# SAMD21E-breakout.net
KiCad netlist of a schematic drawn in EAGLE
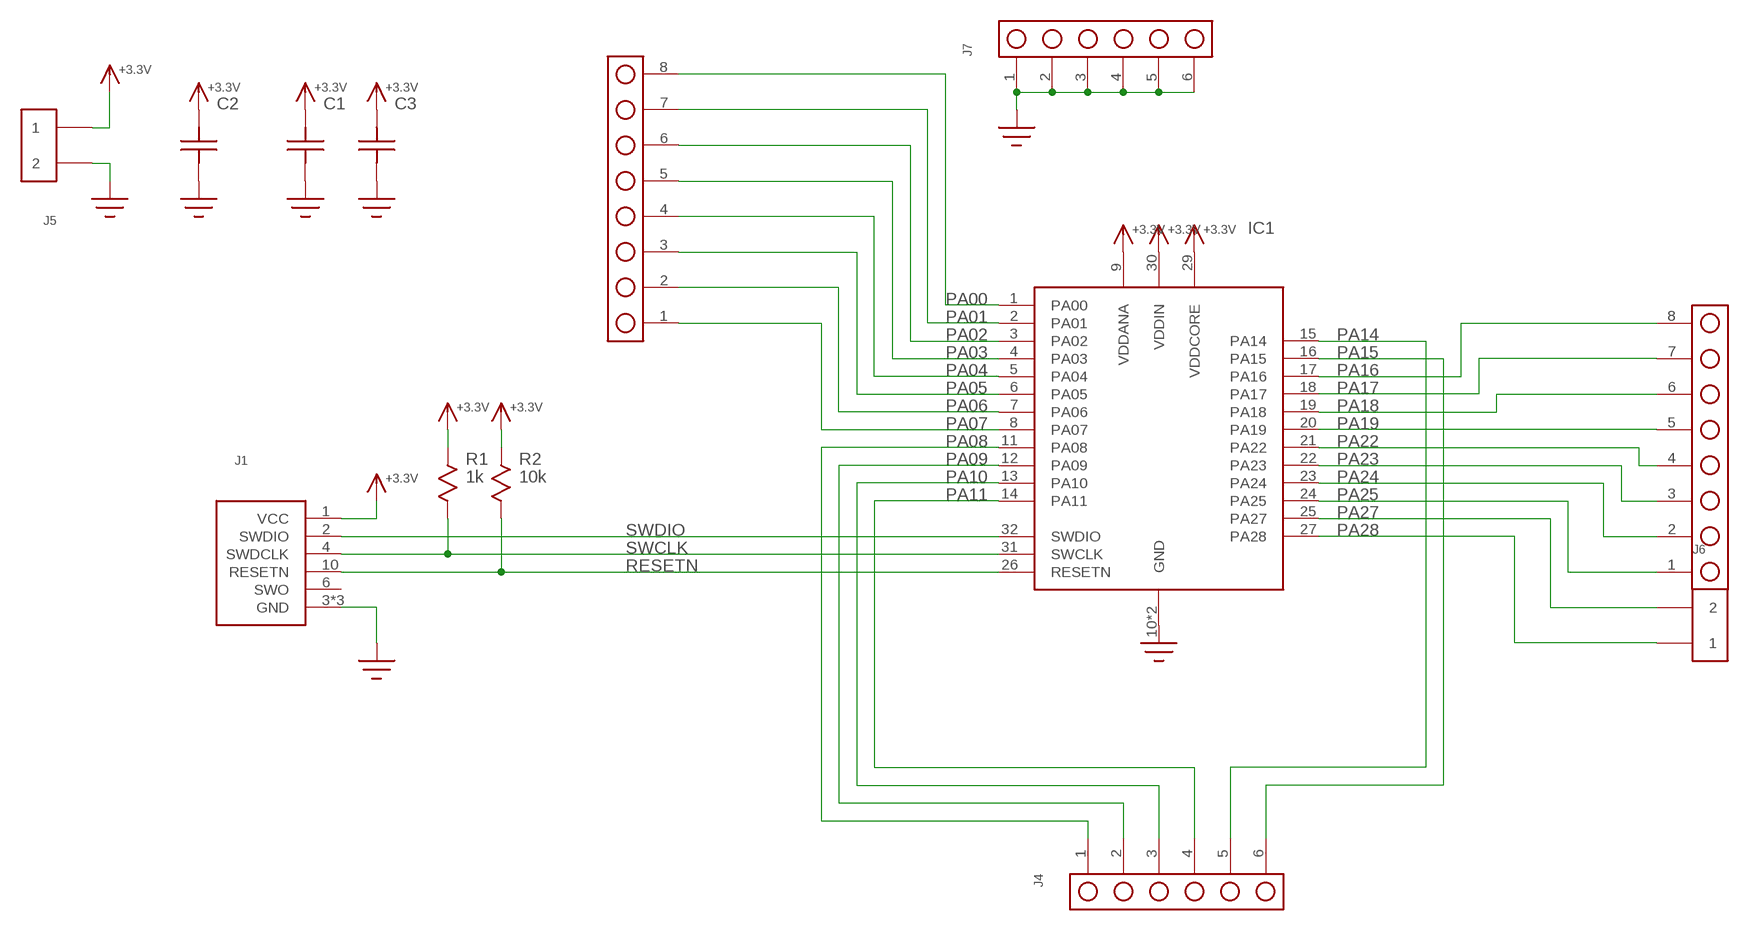
[diagram p0: schematic, sheet 1]

(export (version "E")
  (design (tool "Eeschema 10.0.6"))
  (components
    (comp (ref "C1")
      (value "C0603")
      (footprint "eagle-import:C0603")
      (libsource (lib "eagle-import") (part "C0603"))
    )
    (comp (ref "C2")
      (value "C1206")
      (footprint "eagle-import:1206")
      (libsource (lib "eagle-import") (part "C1206"))
    )
    (comp (ref "C3")
      (value "C0603")
      (footprint "eagle-import:C0603")
      (libsource (lib "eagle-import") (part "C0603"))
    )
    (comp (ref "IC1")
      (value "SAMD21E")
      (footprint "eagle-import:TQFP32_7X7")
      (libsource (lib "eagle-import") (part "SAMD21E"))
    )
    (comp (ref "J1")
      (value "SWD-ICSP-HEADER")
      (footprint "eagle-import:HEADER-2X5-50MIL")
      (libsource (lib "eagle-import") (part "SWD-ICSP-HEADER"))
    )
    (comp (ref "J2")
      (value "HEADER_8PIN")
      (footprint "eagle-import:HEADER_8_PIN")
      (libsource (lib "eagle-import") (part "HEADER_8PIN"))
    )
    (comp (ref "J3")
      (value "HEADER_8PIN")
      (footprint "eagle-import:HEADER_8_PIN")
      (libsource (lib "eagle-import") (part "HEADER_8PIN"))
    )
    (comp (ref "J4")
      (value "HEADER_6PIN")
      (footprint "eagle-import:HEADER_6PIN")
      (libsource (lib "eagle-import") (part "HEADER_6PIN"))
    )
    (comp (ref "J5")
      (value "HEADER_2PIN")
      (footprint "eagle-import:HEADER_2PIN")
      (libsource (lib "eagle-import") (part "HEADER_2PIN"))
    )
    (comp (ref "J6")
      (value "HEADER_2PIN")
      (footprint "eagle-import:HEADER_2PIN")
      (libsource (lib "eagle-import") (part "HEADER_2PIN"))
    )
    (comp (ref "J7")
      (value "HEADER_6PIN")
      (footprint "eagle-import:HEADER_6PIN")
      (libsource (lib "eagle-import") (part "HEADER_6PIN"))
    )
    (comp (ref "R1")
      (value "1k")
      (footprint "eagle-import:R0603")
      (libsource (lib "eagle-import") (part "R0603"))
    )
    (comp (ref "R2")
      (value "10k")
      (footprint "eagle-import:R0603")
      (libsource (lib "eagle-import") (part "R0603"))
    )
  )
  (nets
    (net (code "1") (name "+3.3V") (class "Default")
      (node (ref "C1") (pin "P$2") (pinfunction "P$2_P$2") (pintype "bidirectional"))
      (node (ref "C2") (pin "P$2") (pinfunction "P$2_P$2") (pintype "bidirectional"))
      (node (ref "C3") (pin "P$2") (pinfunction "P$2_P$2") (pintype "bidirectional"))
      (node (ref "IC1") (pin "29") (pinfunction "VDDCORE_29") (pintype "bidirectional"))
      (node (ref "IC1") (pin "30") (pinfunction "VDDIN_30") (pintype "bidirectional"))
      (node (ref "IC1") (pin "9") (pinfunction "VDDANA_9") (pintype "bidirectional"))
      (node (ref "J1") (pin "1") (pinfunction "VCC_1") (pintype "bidirectional"))
      (node (ref "J5") (pin "1") (pinfunction "1_1") (pintype "bidirectional"))
      (node (ref "R1") (pin "P$1") (pinfunction "P$3_P$1") (pintype "bidirectional"))
      (node (ref "R2") (pin "P$1") (pinfunction "P$3_P$1") (pintype "bidirectional"))
    )
    (net (code "2") (name "/PA00") (class "Default")
      (node (ref "IC1") (pin "1") (pinfunction "PA00_1") (pintype "bidirectional"))
      (node (ref "J2") (pin "8") (pinfunction "8_8") (pintype "bidirectional"))
    )
    (net (code "3") (name "/PA01") (class "Default")
      (node (ref "IC1") (pin "2") (pinfunction "PA01_2") (pintype "bidirectional"))
      (node (ref "J2") (pin "7") (pinfunction "7_7") (pintype "bidirectional"))
    )
    (net (code "4") (name "/PA02") (class "Default")
      (node (ref "IC1") (pin "3") (pinfunction "PA02_3") (pintype "bidirectional"))
      (node (ref "J2") (pin "6") (pinfunction "6_6") (pintype "bidirectional"))
    )
    (net (code "5") (name "/PA03") (class "Default")
      (node (ref "IC1") (pin "4") (pinfunction "PA03_4") (pintype "bidirectional"))
      (node (ref "J2") (pin "5") (pinfunction "5_5") (pintype "bidirectional"))
    )
    (net (code "6") (name "/PA04") (class "Default")
      (node (ref "IC1") (pin "5") (pinfunction "PA04_5") (pintype "bidirectional"))
      (node (ref "J2") (pin "4") (pinfunction "4_4") (pintype "bidirectional"))
    )
    (net (code "7") (name "/PA05") (class "Default")
      (node (ref "IC1") (pin "6") (pinfunction "PA05_6") (pintype "bidirectional"))
      (node (ref "J2") (pin "3") (pinfunction "3_3") (pintype "bidirectional"))
    )
    (net (code "8") (name "/PA06") (class "Default")
      (node (ref "IC1") (pin "7") (pinfunction "PA06_7") (pintype "bidirectional"))
      (node (ref "J2") (pin "2") (pinfunction "2_2") (pintype "bidirectional"))
    )
    (net (code "9") (name "/PA07") (class "Default")
      (node (ref "IC1") (pin "8") (pinfunction "PA07_8") (pintype "bidirectional"))
      (node (ref "J2") (pin "1") (pinfunction "1_1") (pintype "bidirectional"))
    )
    (net (code "10") (name "/PA08") (class "Default")
      (node (ref "IC1") (pin "11") (pinfunction "PA08_11") (pintype "bidirectional"))
      (node (ref "J4") (pin "1") (pinfunction "1_1") (pintype "bidirectional"))
    )
    (net (code "11") (name "/PA09") (class "Default")
      (node (ref "IC1") (pin "12") (pinfunction "PA09_12") (pintype "bidirectional"))
      (node (ref "J4") (pin "2") (pinfunction "2_2") (pintype "bidirectional"))
    )
    (net (code "12") (name "/PA10") (class "Default")
      (node (ref "IC1") (pin "13") (pinfunction "PA10_13") (pintype "bidirectional"))
      (node (ref "J4") (pin "3") (pinfunction "3_3") (pintype "bidirectional"))
    )
    (net (code "13") (name "/PA11") (class "Default")
      (node (ref "IC1") (pin "14") (pinfunction "PA11_14") (pintype "bidirectional"))
      (node (ref "J4") (pin "4") (pinfunction "4_4") (pintype "bidirectional"))
    )
    (net (code "14") (name "/PA14") (class "Default")
      (node (ref "IC1") (pin "15") (pinfunction "PA14_15") (pintype "bidirectional"))
      (node (ref "J4") (pin "5") (pinfunction "5_5") (pintype "bidirectional"))
    )
    (net (code "15") (name "/PA15") (class "Default")
      (node (ref "IC1") (pin "16") (pinfunction "PA15_16") (pintype "bidirectional"))
      (node (ref "J4") (pin "6") (pinfunction "6_6") (pintype "bidirectional"))
    )
    (net (code "16") (name "/PA16") (class "Default")
      (node (ref "IC1") (pin "17") (pinfunction "PA16_17") (pintype "bidirectional"))
      (node (ref "J3") (pin "8") (pinfunction "8_8") (pintype "bidirectional"))
    )
    (net (code "17") (name "/PA17") (class "Default")
      (node (ref "IC1") (pin "18") (pinfunction "PA17_18") (pintype "bidirectional"))
      (node (ref "J3") (pin "7") (pinfunction "7_7") (pintype "bidirectional"))
    )
    (net (code "18") (name "/PA18") (class "Default")
      (node (ref "IC1") (pin "19") (pinfunction "PA18_19") (pintype "bidirectional"))
      (node (ref "J3") (pin "6") (pinfunction "6_6") (pintype "bidirectional"))
    )
    (net (code "19") (name "/PA19") (class "Default")
      (node (ref "IC1") (pin "20") (pinfunction "PA19_20") (pintype "bidirectional"))
      (node (ref "J3") (pin "5") (pinfunction "5_5") (pintype "bidirectional"))
    )
    (net (code "20") (name "/PA22") (class "Default")
      (node (ref "IC1") (pin "21") (pinfunction "PA22_21") (pintype "bidirectional"))
      (node (ref "J3") (pin "4") (pinfunction "4_4") (pintype "bidirectional"))
    )
    (net (code "21") (name "/PA23") (class "Default")
      (node (ref "IC1") (pin "22") (pinfunction "PA23_22") (pintype "bidirectional"))
      (node (ref "J3") (pin "3") (pinfunction "3_3") (pintype "bidirectional"))
    )
    (net (code "22") (name "/PA24") (class "Default")
      (node (ref "IC1") (pin "23") (pinfunction "PA24_23") (pintype "bidirectional"))
      (node (ref "J3") (pin "2") (pinfunction "2_2") (pintype "bidirectional"))
    )
    (net (code "23") (name "/PA25") (class "Default")
      (node (ref "IC1") (pin "24") (pinfunction "PA25_24") (pintype "bidirectional"))
      (node (ref "J3") (pin "1") (pinfunction "1_1") (pintype "bidirectional"))
    )
    (net (code "24") (name "/PA27") (class "Default")
      (node (ref "IC1") (pin "25") (pinfunction "PA27_25") (pintype "bidirectional"))
      (node (ref "J6") (pin "2") (pinfunction "2_2") (pintype "bidirectional"))
    )
    (net (code "25") (name "/PA28") (class "Default")
      (node (ref "IC1") (pin "27") (pinfunction "PA28_27") (pintype "bidirectional"))
      (node (ref "J6") (pin "1") (pinfunction "1_1") (pintype "bidirectional"))
    )
    (net (code "26") (name "/RESETN") (class "Default")
      (node (ref "IC1") (pin "26") (pinfunction "RESETN_26") (pintype "bidirectional"))
      (node (ref "J1") (pin "10") (pinfunction "RESETN_10") (pintype "bidirectional"))
      (node (ref "R2") (pin "P$2") (pinfunction "P$4_P$2") (pintype "bidirectional"))
    )
    (net (code "27") (name "/SWCLK") (class "Default")
      (node (ref "IC1") (pin "31") (pinfunction "SWCLK_31") (pintype "bidirectional"))
      (node (ref "J1") (pin "4") (pinfunction "SWDCLK_4") (pintype "bidirectional"))
      (node (ref "R1") (pin "P$2") (pinfunction "P$4_P$2") (pintype "bidirectional"))
    )
    (net (code "28") (name "/SWDIO") (class "Default")
      (node (ref "IC1") (pin "32") (pinfunction "SWDIO_32") (pintype "bidirectional"))
      (node (ref "J1") (pin "2") (pinfunction "SWDIO_2") (pintype "bidirectional"))
    )
    (net (code "29") (name "GND") (class "Default")
      (node (ref "C1") (pin "P$1") (pinfunction "P$1_P$1") (pintype "bidirectional"))
      (node (ref "C2") (pin "P$1") (pinfunction "P$1_P$1") (pintype "bidirectional"))
      (node (ref "C3") (pin "P$1") (pinfunction "P$1_P$1") (pintype "bidirectional"))
      (node (ref "IC1") (pin "10") (pinfunction "GND_10") (pintype "bidirectional"))
      (node (ref "IC1") (pin "28") (pinfunction "GND_28") (pintype "bidirectional"))
      (node (ref "J1") (pin "3") (pinfunction "GND_3") (pintype "bidirectional"))
      (node (ref "J1") (pin "5") (pinfunction "GND_5") (pintype "bidirectional"))
      (node (ref "J1") (pin "9") (pinfunction "GND_9") (pintype "bidirectional"))
      (node (ref "J5") (pin "2") (pinfunction "2_2") (pintype "bidirectional"))
      (node (ref "J7") (pin "1") (pinfunction "1_1") (pintype "bidirectional"))
      (node (ref "J7") (pin "2") (pinfunction "2_2") (pintype "bidirectional"))
      (node (ref "J7") (pin "3") (pinfunction "3_3") (pintype "bidirectional"))
      (node (ref "J7") (pin "4") (pinfunction "4_4") (pintype "bidirectional"))
      (node (ref "J7") (pin "5") (pinfunction "5_5") (pintype "bidirectional"))
      (node (ref "J7") (pin "6") (pinfunction "6_6") (pintype "bidirectional"))
    )
    (net (code "30") (name "unconnected-(J1-SWO-Pad6)") (class "Default")
      (node (ref "J1") (pin "6") (pinfunction "SWO_6") (pintype "bidirectional"))
    )
  )
)
